# PowerSplitter.net
KiCad netlist of a schematic drawn in Altium Designer
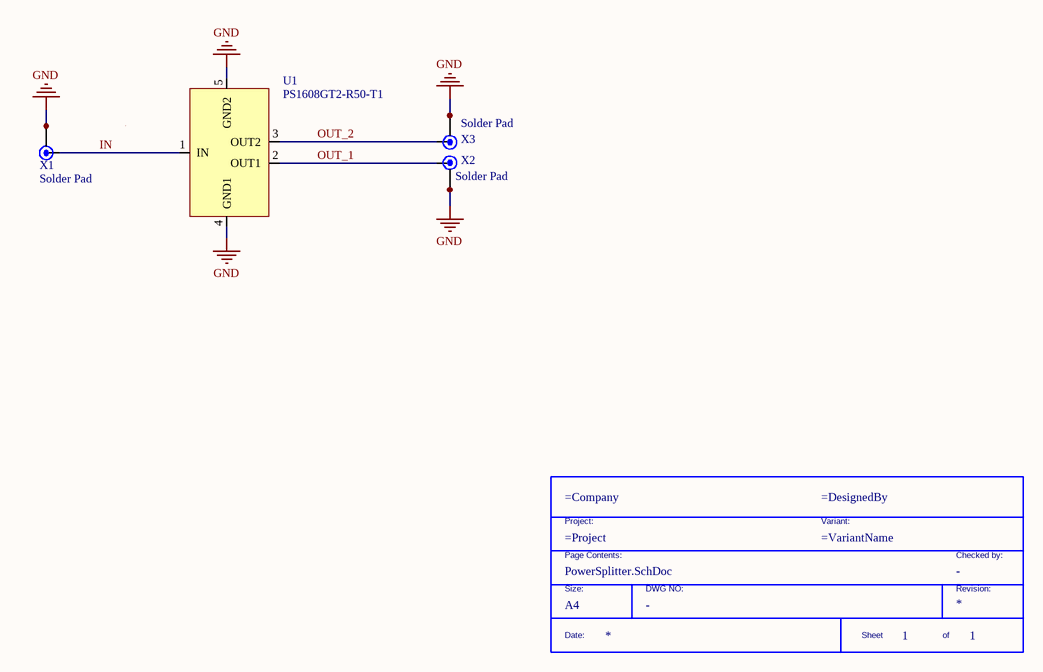
[diagram p0: PowerSplitter.SchDoc]

(export (version "E")
  (design (tool "Eeschema 10.0.6"))
  (components
    (comp (ref "*")
      (value "TitleBlock")
      (description "Standard Title Block")
      (fields (field (name "DWG NO") "-") (field (name "SIZE") "A4") (field (name "CHECKED BY") "-"))
      (libsource (lib "PowerSplitter") (part "TitleBlock"))
    )
    (comp (ref "U1")
      (value "PS1608GT2-R50-T1")
      (footprint "PS1608GT2-R50-T1")
      (description "Splitter, 0MHz Min, 20000MHz Max, 6dB Insertion Loss-Max")
      (fields (field (name "MANUFACTURER") "Susumu"))
      (libsource (lib "PowerSplitter") (part "PS1608GT2-R50-T1"))
    )
    (comp (ref "X1")
      (value "Solder Pad")
      (footprint "CPW Edge Connector")
      (description "Solder pad for RF Coplanar Waveguide Rogers 4350B Thickness 0.020\" Copper 1oz")
      (libsource (lib "PowerSplitter") (part "RF  CPW Solder Pad"))
    )
    (comp (ref "X2")
      (value "Solder Pad")
      (footprint "CPW Edge Connector")
      (description "Solder pad for RF Coplanar Waveguide Rogers 4350B Thickness 0.020\" Copper 1oz")
      (libsource (lib "PowerSplitter") (part "RF  CPW Solder Pad"))
    )
    (comp (ref "X3")
      (value "Solder Pad")
      (footprint "CPW Edge Connector")
      (description "Solder pad for RF Coplanar Waveguide Rogers 4350B Thickness 0.020\" Copper 1oz")
      (libsource (lib "PowerSplitter") (part "RF  CPW Solder Pad"))
    )
  )
  (nets
    (net (code "1") (name "/IN") (class "Default")
      (node (ref "U1") (pin "1") (pinfunction "IN_1") (pintype "passive"))
      (node (ref "X1") (pin "1") (pinfunction "1_1") (pintype "passive"))
    )
    (net (code "2") (name "/OUT_1") (class "Default")
      (node (ref "U1") (pin "2") (pinfunction "OUT1_2") (pintype "passive"))
      (node (ref "X2") (pin "1") (pinfunction "1_1") (pintype "passive"))
    )
    (net (code "3") (name "/OUT_2") (class "Default")
      (node (ref "U1") (pin "3") (pinfunction "OUT2_3") (pintype "passive"))
      (node (ref "X3") (pin "1") (pinfunction "1_1") (pintype "passive"))
    )
    (net (code "4") (name "GND") (class "Default")
      (node (ref "U1") (pin "4") (pinfunction "GND1_4") (pintype "passive"))
      (node (ref "U1") (pin "5") (pinfunction "GND2_5") (pintype "passive"))
      (node (ref "X1") (pin "2") (pinfunction "2_2") (pintype "passive"))
      (node (ref "X1") (pin "3") (pinfunction "3_3") (pintype "passive"))
      (node (ref "X2") (pin "2") (pinfunction "2_2") (pintype "passive"))
      (node (ref "X2") (pin "3") (pinfunction "3_3") (pintype "passive"))
      (node (ref "X3") (pin "2") (pinfunction "2_2") (pintype "passive"))
      (node (ref "X3") (pin "3") (pinfunction "3_3") (pintype "passive"))
    )
  )
)
